# WAB_1_1_top_level.net
KiCad netlist of a schematic drawn in Altium Designer
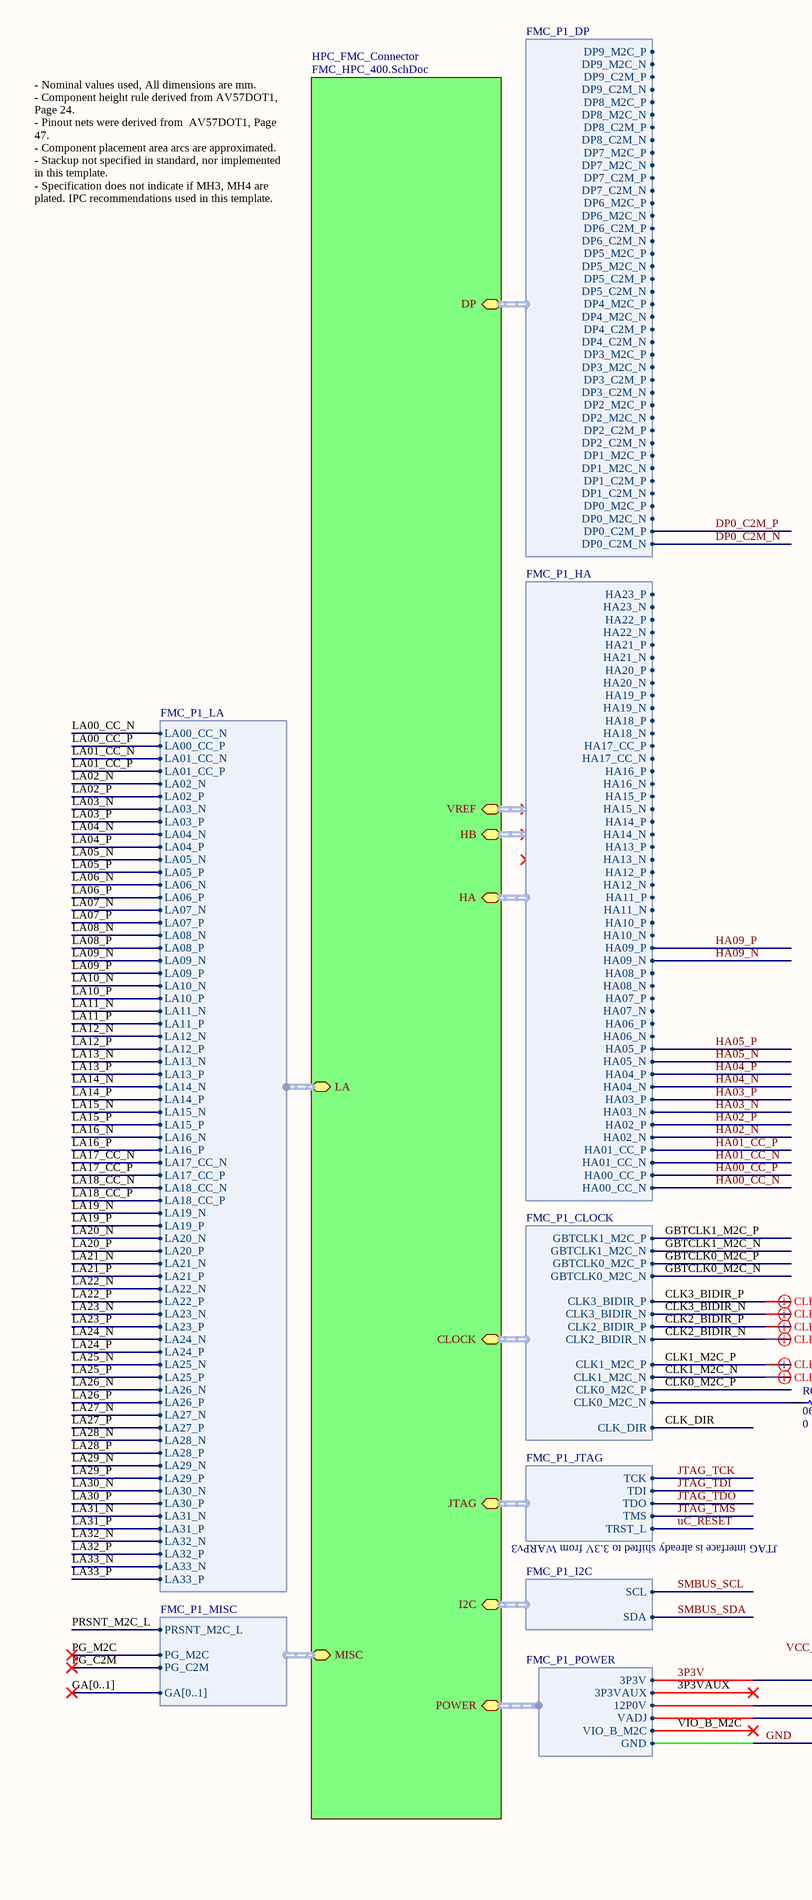
[diagram p0: WAB_1_1_top_level.SchDoc, left]
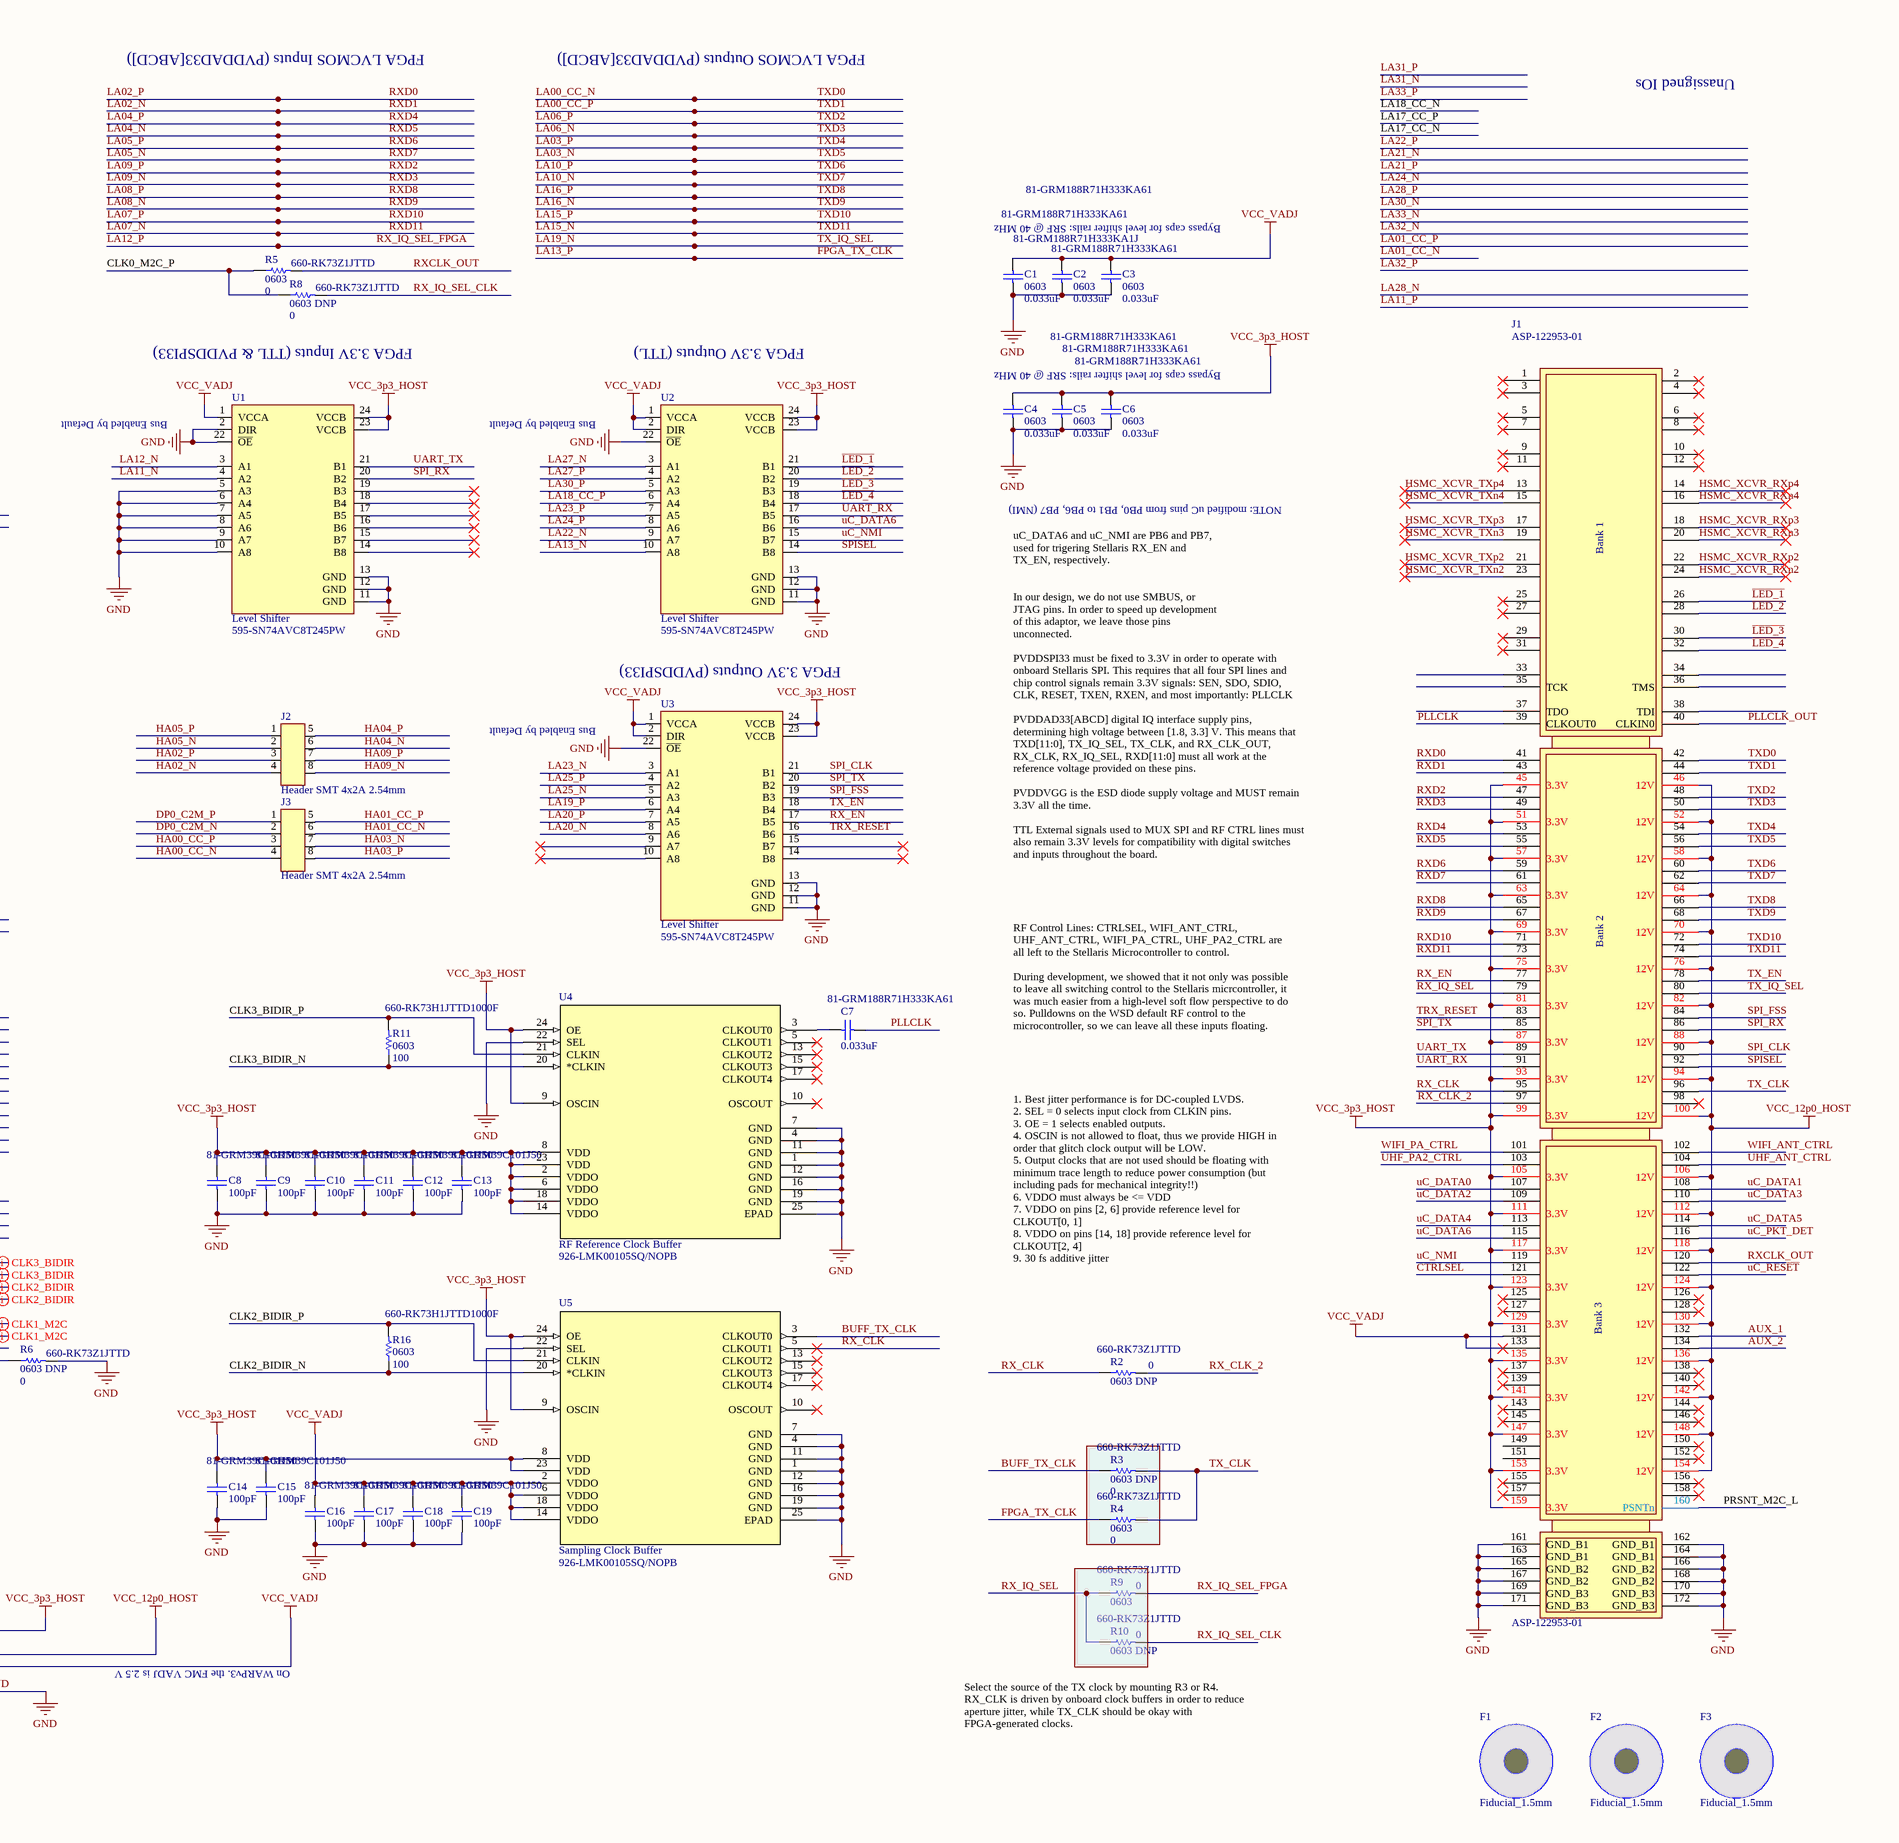
[diagram p1: WAB_1_1_top_level.SchDoc, right]

(export (version "E")
  (design (tool "Eeschema 10.0.6"))
  (components
    (comp (ref "C1")
      (value "0603")
      (footprint "RNG_Footprints:0603_SMT_v3")
      (description "Capacitor (Semiconductor SIM Model)")
      (fields
        (field (name "ALTIUM_VALUE") "0.033uF")
        (field (name "SUPPLIER PART NUMBER 1") "81-GRM188R71H333KA1J")
        (field (name "SUPPLIER PART NUMBER 2") "81-GRM188R71H333KA61")
      )
      (libsource (lib "Miscellaneous Devices") (part "Cap Semi"))
    )
    (comp (ref "C2")
      (value "0603")
      (footprint "RNG_Footprints:0603_SMT_v3")
      (description "Capacitor (Semiconductor SIM Model)")
      (fields
        (field (name "ALTIUM_VALUE") "0.033uF")
        (field (name "SUPPLIER PART NUMBER 2") "81-GRM188R71H333KA61")
      )
      (libsource (lib "Miscellaneous Devices") (part "Cap Semi"))
    )
    (comp (ref "C3")
      (value "0603")
      (footprint "RNG_Footprints:0603_SMT_v3")
      (description "Capacitor (Semiconductor SIM Model)")
      (fields
        (field (name "ALTIUM_VALUE") "0.033uF")
        (field (name "SUPPLIER PART NUMBER 2") "81-GRM188R71H333KA61")
      )
      (libsource (lib "Miscellaneous Devices") (part "Cap Semi"))
    )
    (comp (ref "C4")
      (value "0603")
      (footprint "RNG_Footprints:0603_SMT_v3")
      (description "Capacitor (Semiconductor SIM Model)")
      (fields
        (field (name "ALTIUM_VALUE") "0.033uF")
        (field (name "SUPPLIER PART NUMBER 2") "81-GRM188R71H333KA61")
      )
      (libsource (lib "Miscellaneous Devices") (part "Cap Semi"))
    )
    (comp (ref "C5")
      (value "0603")
      (footprint "RNG_Footprints:0603_SMT_v3")
      (description "Capacitor (Semiconductor SIM Model)")
      (fields
        (field (name "ALTIUM_VALUE") "0.033uF")
        (field (name "SUPPLIER PART NUMBER 2") "81-GRM188R71H333KA61")
      )
      (libsource (lib "Miscellaneous Devices") (part "Cap Semi"))
    )
    (comp (ref "C6")
      (value "0603")
      (footprint "RNG_Footprints:0603_SMT_v3")
      (description "Capacitor (Semiconductor SIM Model)")
      (fields
        (field (name "ALTIUM_VALUE") "0.033uF")
        (field (name "SUPPLIER PART NUMBER 2") "81-GRM188R71H333KA61")
      )
      (libsource (lib "Miscellaneous Devices") (part "Cap Semi"))
    )
    (comp (ref "C7")
      (value "0.033uF")
      (footprint "0603_SMT_v3")
      (fields (field (name "SUPPLIER PART NUMBER 1") "81-GRM188R71H333KA61") (field (name "Comment") "0603"))
      (libsource (lib "RNG_Parts") (part "Cap_0603"))
    )
    (comp (ref "C8")
      (value "100pF")
      (footprint "0603_SMT_v3")
      (fields (field (name "SUPPLIER PART NUMBER 1") "81-GRM39C101J50") (field (name "Comment") "0603"))
      (libsource (lib "RNG_Parts") (part "Cap_0603"))
    )
    (comp (ref "C9")
      (value "100pF")
      (footprint "0603_SMT_v3")
      (fields (field (name "SUPPLIER PART NUMBER 1") "81-GRM39C101J50") (field (name "Comment") "0603"))
      (libsource (lib "RNG_Parts") (part "Cap_0603"))
    )
    (comp (ref "C10")
      (value "100pF")
      (footprint "0603_SMT_v3")
      (fields (field (name "SUPPLIER PART NUMBER 1") "81-GRM39C101J50") (field (name "Comment") "0603"))
      (libsource (lib "RNG_Parts") (part "Cap_0603"))
    )
    (comp (ref "C11")
      (value "100pF")
      (footprint "0603_SMT_v3")
      (fields (field (name "SUPPLIER PART NUMBER 1") "81-GRM39C101J50") (field (name "Comment") "0603"))
      (libsource (lib "RNG_Parts") (part "Cap_0603"))
    )
    (comp (ref "C12")
      (value "100pF")
      (footprint "0603_SMT_v3")
      (fields (field (name "SUPPLIER PART NUMBER 1") "81-GRM39C101J50") (field (name "Comment") "0603"))
      (libsource (lib "RNG_Parts") (part "Cap_0603"))
    )
    (comp (ref "C13")
      (value "100pF")
      (footprint "0603_SMT_v3")
      (fields (field (name "SUPPLIER PART NUMBER 1") "81-GRM39C101J50") (field (name "Comment") "0603"))
      (libsource (lib "RNG_Parts") (part "Cap_0603"))
    )
    (comp (ref "C14")
      (value "100pF")
      (footprint "0603_SMT_v3")
      (fields (field (name "SUPPLIER PART NUMBER 1") "81-GRM39C101J50") (field (name "Comment") "0603"))
      (libsource (lib "RNG_Parts") (part "Cap_0603"))
    )
    (comp (ref "C15")
      (value "100pF")
      (footprint "0603_SMT_v3")
      (fields (field (name "SUPPLIER PART NUMBER 1") "81-GRM39C101J50") (field (name "Comment") "0603"))
      (libsource (lib "RNG_Parts") (part "Cap_0603"))
    )
    (comp (ref "C16")
      (value "100pF")
      (footprint "0603_SMT_v3")
      (fields (field (name "SUPPLIER PART NUMBER 1") "81-GRM39C101J50") (field (name "Comment") "0603"))
      (libsource (lib "RNG_Parts") (part "Cap_0603"))
    )
    (comp (ref "C17")
      (value "100pF")
      (footprint "0603_SMT_v3")
      (fields (field (name "SUPPLIER PART NUMBER 1") "81-GRM39C101J50") (field (name "Comment") "0603"))
      (libsource (lib "RNG_Parts") (part "Cap_0603"))
    )
    (comp (ref "C18")
      (value "100pF")
      (footprint "0603_SMT_v3")
      (fields (field (name "SUPPLIER PART NUMBER 1") "81-GRM39C101J50") (field (name "Comment") "0603"))
      (libsource (lib "RNG_Parts") (part "Cap_0603"))
    )
    (comp (ref "C19")
      (value "100pF")
      (footprint "0603_SMT_v3")
      (fields (field (name "SUPPLIER PART NUMBER 1") "81-GRM39C101J50") (field (name "Comment") "0603"))
      (libsource (lib "RNG_Parts") (part "Cap_0603"))
    )
    (comp (ref "F1")
      (value "Fiducial_1.5mm")
      (footprint "1.5mm_FIDUCIAL_v4")
      (libsource (lib "RNG_Parts") (part "Fiducial_1.5mm"))
    )
    (comp (ref "F2")
      (value "Fiducial_1.5mm")
      (footprint "1.5mm_FIDUCIAL_v4")
      (libsource (lib "RNG_Parts") (part "Fiducial_1.5mm"))
    )
    (comp (ref "F3")
      (value "Fiducial_1.5mm")
      (footprint "1.5mm_FIDUCIAL_v4")
      (libsource (lib "RNG_Parts") (part "Fiducial_1.5mm"))
    )
    (comp (ref "J1")
      (value "ASP-122953-01")
      (footprint "ASP-122953-01_v2")
      (description "Samtec HSMC Host Connector (Female)")
      (libsource (lib "RNG_Parts") (part "ASP-122953-01"))
    )
    (comp (ref "J2")
      (value "Header SMT 4x2A 2.54mm")
      (footprint "2.54mm_4x2_HDR")
      (libsource (lib "RNG_Parts") (part "Header SMT 4x2A 2.54mm"))
    )
    (comp (ref "J3")
      (value "Header SMT 4x2A 2.54mm")
      (footprint "2.54mm_4x2_HDR")
      (libsource (lib "RNG_Parts") (part "Header SMT 4x2A 2.54mm"))
    )
    (comp (ref "R2")
      (value "0603 DNP")
      (footprint "0603_SMT_v3")
      (description "0603 SMT Resistor")
      (fields (field (name "ALTIUM_VALUE") "0") (field (name "SUPPLIER PART NUMBER 1") "660-RK73Z1JTTD"))
      (libsource (lib "RNG_Parts") (part "Res_0603"))
    )
    (comp (ref "R3")
      (value "0603 DNP")
      (footprint "0603_SMT_v3")
      (description "0603 SMT Resistor")
      (fields (field (name "ALTIUM_VALUE") "0") (field (name "SUPPLIER PART NUMBER 1") "660-RK73Z1JTTD"))
      (libsource (lib "RNG_Parts") (part "Res_0603"))
    )
    (comp (ref "R4")
      (value "0603")
      (footprint "0603_SMT_v3")
      (description "0603 SMT Resistor")
      (fields (field (name "ALTIUM_VALUE") "0") (field (name "SUPPLIER PART NUMBER 1") "660-RK73Z1JTTD"))
      (libsource (lib "RNG_Parts") (part "Res_0603"))
    )
    (comp (ref "R5")
      (value "0603")
      (footprint "0603_SMT_v3")
      (description "0603 SMT Resistor")
      (fields (field (name "ALTIUM_VALUE") "0") (field (name "SUPPLIER PART NUMBER 1") "660-RK73Z1JTTD"))
      (libsource (lib "RNG_Parts") (part "Res_0603"))
    )
    (comp (ref "R6")
      (value "0603 DNP")
      (footprint "0603_SMT_v3")
      (description "0603 SMT Resistor")
      (fields (field (name "ALTIUM_VALUE") "0") (field (name "SUPPLIER PART NUMBER 1") "660-RK73Z1JTTD"))
      (libsource (lib "RNG_Parts") (part "Res_0603"))
    )
    (comp (ref "R8")
      (value "0603 DNP")
      (footprint "0603_SMT_v3")
      (description "0603 SMT Resistor")
      (fields (field (name "ALTIUM_VALUE") "0") (field (name "SUPPLIER PART NUMBER 1") "660-RK73Z1JTTD"))
      (libsource (lib "RNG_Parts") (part "Res_0603"))
    )
    (comp (ref "R9")
      (value "0603")
      (footprint "0603_SMT_v3")
      (description "0603 SMT Resistor")
      (fields (field (name "ALTIUM_VALUE") "0") (field (name "SUPPLIER PART NUMBER 1") "660-RK73Z1JTTD"))
      (libsource (lib "RNG_Parts") (part "Res_0603"))
    )
    (comp (ref "R10")
      (value "0603 DNP")
      (footprint "0603_SMT_v3")
      (description "0603 SMT Resistor")
      (fields (field (name "ALTIUM_VALUE") "0") (field (name "SUPPLIER PART NUMBER 1") "660-RK73Z1JTTD"))
      (libsource (lib "RNG_Parts") (part "Res_0603"))
    )
    (comp (ref "R11")
      (value "0603")
      (footprint "0603_SMT_v3")
      (description "0603 SMT Resistor")
      (fields
        (field (name "ALTIUM_VALUE") "100")
        (field (name "SUPPLIER PART NUMBER 1") "660-RK73H1JTTD1000F")
      )
      (libsource (lib "RNG_Parts") (part "Res_0603"))
    )
    (comp (ref "R16")
      (value "0603")
      (footprint "0603_SMT_v3")
      (description "0603 SMT Resistor")
      (fields
        (field (name "ALTIUM_VALUE") "100")
        (field (name "SUPPLIER PART NUMBER 1") "660-RK73H1JTTD1000F")
      )
      (libsource (lib "RNG_Parts") (part "Res_0603"))
    )
    (comp (ref "U1")
      (value "Level Shifter")
      (footprint "TSSOP-24_TI")
      (description "8-bit Dual Supply Bus Transceiver")
      (fields (field (name "SUPPLIER PART NUMBER 1") "595-SN74AVC8T245PW"))
      (libsource (lib "RNG_Parts") (part "SN74AVC8T245PW"))
    )
    (comp (ref "U2")
      (value "Level Shifter")
      (footprint "TSSOP-24_TI")
      (description "8-bit Dual Supply Bus Transceiver")
      (fields (field (name "SUPPLIER PART NUMBER 1") "595-SN74AVC8T245PW"))
      (libsource (lib "RNG_Parts") (part "SN74AVC8T245PW"))
    )
    (comp (ref "U3")
      (value "Level Shifter")
      (footprint "TSSOP-24_TI")
      (description "8-bit Dual Supply Bus Transceiver")
      (fields (field (name "SUPPLIER PART NUMBER 1") "595-SN74AVC8T245PW"))
      (libsource (lib "RNG_Parts") (part "SN74AVC8T245PW"))
    )
    (comp (ref "U4")
      (value "RF Reference Clock Buffer")
      (footprint "RTW24")
      (description "TI Universal-to-CMOS 5-Output Clock Buffer")
      (fields
        (field (name "MANUFACTURER_PART_NUMBER") "lmk00105_rtw_24")
        (field (name "SUPPLIER PART NUMBER 1") "926-LMK00105SQ/NOPB")
      )
      (libsource (lib "RNG_Parts") (part "LMK00105_RTW_24"))
    )
    (comp (ref "U5")
      (value "Sampling Clock Buffer")
      (footprint "RTW24")
      (description "TI Universal-to-CMOS 5-Output Clock Buffer")
      (fields
        (field (name "MANUFACTURER_PART_NUMBER") "lmk00105_rtw_24")
        (field (name "SUPPLIER PART NUMBER 1") "926-LMK00105SQ/NOPB")
      )
      (libsource (lib "RNG_Parts") (part "LMK00105_RTW_24"))
    )
  )
  (nets
    (net (code "12") (name "/AUX_1") (class "Default")
      (node (ref "J1") (pin "132") (pinfunction "132_132") (pintype "passive"))
    )
    (net (code "13") (name "/AUX_2") (class "Default")
      (node (ref "J1") (pin "134") (pinfunction "134_134") (pintype "passive"))
    )
    (net (code "14") (name "/BUFF_TX_CLK") (class "Default")
      (node (ref "R3") (pin "1") (pinfunction "1_1") (pintype "passive"))
      (node (ref "U5") (pin "3") (pinfunction "CLKOUT0_3") (pintype "output"))
    )
    (net (code "15") (name "/CLK0_M2C_N") (class "Default")
      (node (ref "R6") (pin "1") (pinfunction "1_1") (pintype "passive"))
    )
    (net (code "16") (name "/CLK0_M2C_P") (class "Default")
      (node (ref "R5") (pin "1") (pinfunction "1_1") (pintype "passive"))
      (node (ref "R8") (pin "1") (pinfunction "1_1") (pintype "passive"))
    )
    (net (code "19") (name "/CLK2_BIDIR_N") (class "Default")
      (node (ref "R16") (pin "1") (pinfunction "1_1") (pintype "passive"))
      (node (ref "U5") (pin "20") (pinfunction "*CLKIN_20") (pintype "input"))
    )
    (net (code "20") (name "/CLK2_BIDIR_P") (class "Default")
      (node (ref "R16") (pin "2") (pinfunction "2_2") (pintype "passive"))
      (node (ref "U5") (pin "21") (pinfunction "CLKIN_21") (pintype "input"))
    )
    (net (code "21") (name "/CLK3_BIDIR_N") (class "Default")
      (node (ref "R11") (pin "1") (pinfunction "1_1") (pintype "passive"))
      (node (ref "U4") (pin "20") (pinfunction "*CLKIN_20") (pintype "input"))
    )
    (net (code "22") (name "/CLK3_BIDIR_P") (class "Default")
      (node (ref "R11") (pin "2") (pinfunction "2_2") (pintype "passive"))
      (node (ref "U4") (pin "21") (pinfunction "CLKIN_21") (pintype "input"))
    )
    (net (code "24") (name "/CTRLSEL") (class "Default")
      (node (ref "J1") (pin "121") (pinfunction "121_121") (pintype "passive"))
    )
    (net (code "25") (name "/DP0_C2M_N") (class "Default")
      (node (ref "J3") (pin "2") (pinfunction "2_2") (pintype "passive"))
    )
    (net (code "26") (name "/DP0_C2M_P") (class "Default")
      (node (ref "J3") (pin "1") (pinfunction "1_1") (pintype "passive"))
    )
    (net (code "27") (name "/FPGA_TX_CLK") (class "Default")
      (node (ref "R4") (pin "1") (pinfunction "1_1") (pintype "passive"))
    )
    (net (code "33") (name "/HA00_CC_N") (class "Default")
      (node (ref "J3") (pin "4") (pinfunction "4_4") (pintype "passive"))
    )
    (net (code "34") (name "/HA00_CC_P") (class "Default")
      (node (ref "J3") (pin "3") (pinfunction "3_3") (pintype "passive"))
    )
    (net (code "35") (name "/HA01_CC_N") (class "Default")
      (node (ref "J3") (pin "6") (pinfunction "6_6") (pintype "passive"))
    )
    (net (code "36") (name "/HA01_CC_P") (class "Default")
      (node (ref "J3") (pin "5") (pinfunction "5_5") (pintype "passive"))
    )
    (net (code "37") (name "/HA02_N") (class "Default")
      (node (ref "J2") (pin "4") (pinfunction "4_4") (pintype "passive"))
    )
    (net (code "38") (name "/HA02_P") (class "Default")
      (node (ref "J2") (pin "3") (pinfunction "3_3") (pintype "passive"))
    )
    (net (code "39") (name "/HA03_N") (class "Default")
      (node (ref "J3") (pin "7") (pinfunction "7_7") (pintype "passive"))
    )
    (net (code "40") (name "/HA03_P") (class "Default")
      (node (ref "J3") (pin "8") (pinfunction "8_8") (pintype "passive"))
    )
    (net (code "41") (name "/HA04_N") (class "Default")
      (node (ref "J2") (pin "6") (pinfunction "6_6") (pintype "passive"))
    )
    (net (code "42") (name "/HA04_P") (class "Default")
      (node (ref "J2") (pin "5") (pinfunction "5_5") (pintype "passive"))
    )
    (net (code "43") (name "/HA05_N") (class "Default")
      (node (ref "J2") (pin "2") (pinfunction "2_2") (pintype "passive"))
    )
    (net (code "44") (name "/HA05_P") (class "Default")
      (node (ref "J2") (pin "1") (pinfunction "1_1") (pintype "passive"))
    )
    (net (code "45") (name "/HA09_N") (class "Default")
      (node (ref "J2") (pin "8") (pinfunction "8_8") (pintype "passive"))
    )
    (net (code "46") (name "/HA09_P") (class "Default")
      (node (ref "J2") (pin "7") (pinfunction "7_7") (pintype "passive"))
    )
    (net (code "48") (name "/HSMC_XCVR_RXn2") (class "Default")
      (node (ref "J1") (pin "24") (pinfunction "24_24") (pintype "passive+no_connect"))
    )
    (net (code "49") (name "/HSMC_XCVR_RXn3") (class "Default")
      (node (ref "J1") (pin "20") (pinfunction "20_20") (pintype "passive+no_connect"))
    )
    (net (code "50") (name "/HSMC_XCVR_RXn4") (class "Default")
      (node (ref "J1") (pin "16") (pinfunction "16_16") (pintype "passive+no_connect"))
    )
    (net (code "51") (name "/HSMC_XCVR_RXp2") (class "Default")
      (node (ref "J1") (pin "22") (pinfunction "22_22") (pintype "passive"))
    )
    (net (code "52") (name "/HSMC_XCVR_RXp3") (class "Default")
      (node (ref "J1") (pin "18") (pinfunction "18_18") (pintype "passive+no_connect"))
    )
    (net (code "53") (name "/HSMC_XCVR_RXp4") (class "Default")
      (node (ref "J1") (pin "14") (pinfunction "14_14") (pintype "passive+no_connect"))
    )
    (net (code "54") (name "/HSMC_XCVR_TXn2") (class "Default")
      (node (ref "J1") (pin "23") (pinfunction "23_23") (pintype "passive+no_connect"))
    )
    (net (code "55") (name "/HSMC_XCVR_TXn3") (class "Default")
      (node (ref "J1") (pin "19") (pinfunction "19_19") (pintype "passive+no_connect"))
    )
    (net (code "56") (name "/HSMC_XCVR_TXn4") (class "Default")
      (node (ref "J1") (pin "15") (pinfunction "15_15") (pintype "passive+no_connect"))
    )
    (net (code "57") (name "/HSMC_XCVR_TXp2") (class "Default")
      (node (ref "J1") (pin "21") (pinfunction "21_21") (pintype "passive+no_connect"))
    )
    (net (code "58") (name "/HSMC_XCVR_TXp3") (class "Default")
      (node (ref "J1") (pin "17") (pinfunction "17_17") (pintype "passive+no_connect"))
    )
    (net (code "59") (name "/HSMC_XCVR_TXp4") (class "Default")
      (node (ref "J1") (pin "13") (pinfunction "13_13") (pintype "passive+no_connect"))
    )
    (net (code "64") (name "/LA00_CC_N") (class "Default")
      (node (ref "J1") (pin "42") (pinfunction "42_42") (pintype "passive"))
    )
    (net (code "65") (name "/LA00_CC_P") (class "Default")
      (node (ref "J1") (pin "44") (pinfunction "44_44") (pintype "passive"))
    )
    (net (code "68") (name "/LA02_N") (class "Default")
      (node (ref "J1") (pin "43") (pinfunction "43_43") (pintype "passive"))
    )
    (net (code "69") (name "/LA02_P") (class "Default")
      (node (ref "J1") (pin "41") (pinfunction "41_41") (pintype "passive"))
    )
    (net (code "70") (name "/LA03_N") (class "Default")
      (node (ref "J1") (pin "56") (pinfunction "56_56") (pintype "passive"))
    )
    (net (code "71") (name "/LA03_P") (class "Default")
      (node (ref "J1") (pin "54") (pinfunction "54_54") (pintype "passive"))
    )
    (net (code "72") (name "/LA04_N") (class "Default")
      (node (ref "J1") (pin "55") (pinfunction "55_55") (pintype "passive"))
    )
    (net (code "73") (name "/LA04_P") (class "Default")
      (node (ref "J1") (pin "53") (pinfunction "53_53") (pintype "passive"))
    )
    (net (code "74") (name "/LA05_N") (class "Default")
      (node (ref "J1") (pin "61") (pinfunction "61_61") (pintype "passive"))
    )
    (net (code "75") (name "/LA05_P") (class "Default")
      (node (ref "J1") (pin "59") (pinfunction "59_59") (pintype "passive"))
    )
    (net (code "76") (name "/LA06_N") (class "Default")
      (node (ref "J1") (pin "50") (pinfunction "50_50") (pintype "passive"))
    )
    (net (code "77") (name "/LA06_P") (class "Default")
      (node (ref "J1") (pin "48") (pinfunction "48_48") (pintype "passive"))
    )
    (net (code "78") (name "/LA07_N") (class "Default")
      (node (ref "J1") (pin "73") (pinfunction "73_73") (pintype "passive"))
    )
    (net (code "79") (name "/LA07_P") (class "Default")
      (node (ref "J1") (pin "71") (pinfunction "71_71") (pintype "passive"))
    )
    (net (code "80") (name "/LA08_N") (class "Default")
      (node (ref "J1") (pin "67") (pinfunction "67_67") (pintype "passive"))
    )
    (net (code "81") (name "/LA08_P") (class "Default")
      (node (ref "J1") (pin "65") (pinfunction "65_65") (pintype "passive"))
    )
    (net (code "82") (name "/LA09_N") (class "Default")
      (node (ref "J1") (pin "49") (pinfunction "49_49") (pintype "passive"))
    )
    (net (code "83") (name "/LA09_P") (class "Default")
      (node (ref "J1") (pin "47") (pinfunction "47_47") (pintype "passive"))
    )
    (net (code "84") (name "/LA10_N") (class "Default")
      (node (ref "J1") (pin "62") (pinfunction "62_62") (pintype "passive"))
    )
    (net (code "85") (name "/LA10_P") (class "Default")
      (node (ref "J1") (pin "60") (pinfunction "60_60") (pintype "passive"))
    )
    (net (code "86") (name "/LA11_N") (class "Default")
      (node (ref "U1") (pin "4") (pinfunction "A2_4") (pintype "passive"))
    )
    (net (code "88") (name "/LA12_N") (class "Default")
      (node (ref "U1") (pin "3") (pinfunction "A1_3") (pintype "passive"))
    )
    (net (code "89") (name "/LA12_P") (class "Default")
      (node (ref "R9") (pin "2") (pinfunction "2_2") (pintype "passive"))
    )
    (net (code "90") (name "/LA13_N") (class "Default")
      (node (ref "U2") (pin "10") (pinfunction "A8_10") (pintype "passive"))
    )
    (net (code "93") (name "/LA15_N") (class "Default")
      (node (ref "J1") (pin "74") (pinfunction "74_74") (pintype "passive"))
    )
    (net (code "94") (name "/LA15_P") (class "Default")
      (node (ref "J1") (pin "72") (pinfunction "72_72") (pintype "passive"))
    )
    (net (code "95") (name "/LA16_N") (class "Default")
      (node (ref "J1") (pin "68") (pinfunction "68_68") (pintype "passive"))
    )
    (net (code "96") (name "/LA16_P") (class "Default")
      (node (ref "J1") (pin "66") (pinfunction "66_66") (pintype "passive"))
    )
    (net (code "100") (name "/LA18_CC_P") (class "Default")
      (node (ref "U2") (pin "6") (pinfunction "A4_6") (pintype "passive"))
    )
    (net (code "101") (name "/LA19_N") (class "Default")
      (node (ref "J1") (pin "80") (pinfunction "80_80") (pintype "passive"))
    )
    (net (code "102") (name "/LA19_P") (class "Default")
      (node (ref "U3") (pin "6") (pinfunction "A4_6") (pintype "passive"))
    )
    (net (code "103") (name "/LA20_N") (class "Default")
      (node (ref "U3") (pin "8") (pinfunction "A6_8") (pintype "passive"))
    )
    (net (code "104") (name "/LA20_P") (class "Default")
      (node (ref "U3") (pin "7") (pinfunction "A5_7") (pintype "passive"))
    )
    (net (code "107") (name "/LA22_N") (class "Default")
      (node (ref "U2") (pin "9") (pinfunction "A7_9") (pintype "passive"))
    )
    (net (code "109") (name "/LA23_N") (class "Default")
      (node (ref "U3") (pin "3") (pinfunction "A1_3") (pintype "passive"))
    )
    (net (code "110") (name "/LA23_P") (class "Default")
      (node (ref "U2") (pin "7") (pinfunction "A5_7") (pintype "passive"))
    )
    (net (code "112") (name "/LA24_P") (class "Default")
      (node (ref "U2") (pin "8") (pinfunction "A6_8") (pintype "passive"))
    )
    (net (code "113") (name "/LA25_N") (class "Default")
      (node (ref "U3") (pin "5") (pinfunction "A3_5") (pintype "passive"))
    )
    (net (code "114") (name "/LA25_P") (class "Default")
      (node (ref "U3") (pin "4") (pinfunction "A2_4") (pintype "passive"))
    )
    (net (code "117") (name "/LA27_N") (class "Default")
      (node (ref "U2") (pin "3") (pinfunction "A1_3") (pintype "passive"))
    )
    (net (code "118") (name "/LA27_P") (class "Default")
      (node (ref "U2") (pin "4") (pinfunction "A2_4") (pintype "passive"))
    )
    (net (code "124") (name "/LA30_P") (class "Default")
      (node (ref "U2") (pin "5") (pinfunction "A3_5") (pintype "passive"))
    )
    (net (code "131") (name "/LED_1") (class "Default")
      (node (ref "J1") (pin "26") (pinfunction "26_26") (pintype "passive"))
      (node (ref "U2") (pin "21") (pinfunction "B1_21") (pintype "passive"))
    )
    (net (code "132") (name "/LED_2") (class "Default")
      (node (ref "J1") (pin "28") (pinfunction "28_28") (pintype "passive"))
      (node (ref "U2") (pin "20") (pinfunction "B2_20") (pintype "passive"))
    )
    (net (code "133") (name "/LED_3") (class "Default")
      (node (ref "J1") (pin "30") (pinfunction "30_30") (pintype "passive"))
      (node (ref "U2") (pin "19") (pinfunction "B3_19") (pintype "passive"))
    )
    (net (code "134") (name "/LED_4") (class "Default")
      (node (ref "J1") (pin "32") (pinfunction "32_32") (pintype "passive"))
      (node (ref "U2") (pin "18") (pinfunction "B4_18") (pintype "passive"))
    )
    (net (code "137") (name "/PLLCLK") (class "Default")
      (node (ref "C7") (pin "1") (pinfunction "1_1") (pintype "passive"))
      (node (ref "J1") (pin "39") (pinfunction "CLKOUT0_39") (pintype "power_in"))
    )
    (net (code "138") (name "/PLLCLK_OUT") (class "Default")
      (node (ref "J1") (pin "40") (pinfunction "CLKIN0_40") (pintype "power_in"))
    )
    (net (code "139") (name "/PRSNT_M2C_L") (class "Default")
      (node (ref "J1") (pin "160") (pinfunction "PSNTn_160") (pintype "power_in"))
    )
    (net (code "140") (name "/RXCLK_OUT") (class "Default")
      (node (ref "J1") (pin "120") (pinfunction "120_120") (pintype "passive"))
      (node (ref "R5") (pin "2") (pinfunction "2_2") (pintype "passive"))
    )
    (net (code "141") (name "/RX_CLK") (class "Default")
      (node (ref "J1") (pin "95") (pinfunction "95_95") (pintype "passive"))
      (node (ref "R2") (pin "1") (pinfunction "1_1") (pintype "passive"))
      (node (ref "U5") (pin "5") (pinfunction "CLKOUT1_5") (pintype "output"))
    )
    (net (code "142") (name "/RX_CLK_2") (class "Default")
      (node (ref "J1") (pin "97") (pinfunction "97_97") (pintype "passive"))
      (node (ref "R2") (pin "2") (pinfunction "2_2") (pintype "passive"))
    )
    (net (code "143") (name "/RX_EN") (class "Default")
      (node (ref "J1") (pin "77") (pinfunction "77_77") (pintype "passive"))
      (node (ref "U3") (pin "17") (pinfunction "B5_17") (pintype "passive"))
    )
    (net (code "144") (name "/RX_IQ_SEL") (class "Default")
      (node (ref "J1") (pin "79") (pinfunction "79_79") (pintype "passive"))
      (node (ref "R10") (pin "1") (pinfunction "1_1") (pintype "passive"))
      (node (ref "R9") (pin "1") (pinfunction "1_1") (pintype "passive"))
    )
    (net (code "145") (name "/RX_IQ_SEL_CLK") (class "Default")
      (node (ref "R10") (pin "2") (pinfunction "2_2") (pintype "passive"))
      (node (ref "R8") (pin "2") (pinfunction "2_2") (pintype "passive"))
    )
    (net (code "148") (name "/SPISEL") (class "Default")
      (node (ref "J1") (pin "92") (pinfunction "92_92") (pintype "passive"))
      (node (ref "U2") (pin "14") (pinfunction "B8_14") (pintype "passive"))
    )
    (net (code "149") (name "/SPI_CLK") (class "Default")
      (node (ref "J1") (pin "90") (pinfunction "90_90") (pintype "passive"))
      (node (ref "U3") (pin "21") (pinfunction "B1_21") (pintype "passive"))
    )
    (net (code "150") (name "/SPI_FSS") (class "Default")
      (node (ref "J1") (pin "84") (pinfunction "84_84") (pintype "passive"))
      (node (ref "U3") (pin "19") (pinfunction "B3_19") (pintype "passive"))
    )
    (net (code "151") (name "/SPI_RX") (class "Default")
      (node (ref "J1") (pin "86") (pinfunction "86_86") (pintype "passive"))
      (node (ref "U1") (pin "20") (pinfunction "B2_20") (pintype "passive"))
    )
    (net (code "152") (name "/SPI_TX") (class "Default")
      (node (ref "J1") (pin "85") (pinfunction "85_85") (pintype "passive"))
      (node (ref "U3") (pin "20") (pinfunction "B2_20") (pintype "passive"))
    )
    (net (code "153") (name "/TRX_RESET") (class "Default")
      (node (ref "J1") (pin "83") (pinfunction "83_83") (pintype "passive"))
      (node (ref "U3") (pin "16") (pinfunction "B6_16") (pintype "passive"))
    )
    (net (code "154") (name "/TX_CLK") (class "Default")
      (node (ref "J1") (pin "96") (pinfunction "96_96") (pintype "passive"))
      (node (ref "R3") (pin "2") (pinfunction "2_2") (pintype "passive"))
      (node (ref "R4") (pin "2") (pinfunction "2_2") (pintype "passive"))
    )
    (net (code "155") (name "/TX_EN") (class "Default")
      (node (ref "J1") (pin "78") (pinfunction "78_78") (pintype "passive"))
      (node (ref "U3") (pin "18") (pinfunction "B4_18") (pintype "passive"))
    )
    (net (code "156") (name "/UART_RX") (class "Default")
      (node (ref "J1") (pin "91") (pinfunction "91_91") (pintype "passive"))
      (node (ref "U2") (pin "17") (pinfunction "B5_17") (pintype "passive"))
    )
    (net (code "157") (name "/UART_TX") (class "Default")
      (node (ref "J1") (pin "89") (pinfunction "89_89") (pintype "passive"))
      (node (ref "U1") (pin "21") (pinfunction "B1_21") (pintype "passive"))
    )
    (net (code "158") (name "/UHF_ANT_CTRL") (class "Default")
      (node (ref "J1") (pin "104") (pinfunction "104_104") (pintype "passive"))
    )
    (net (code "159") (name "/UHF_PA2_CTRL") (class "Default")
      (node (ref "J1") (pin "103") (pinfunction "103_103") (pintype "passive"))
    )
    (net (code "162") (name "/WIFI_ANT_CTRL") (class "Default")
      (node (ref "J1") (pin "102") (pinfunction "102_102") (pintype "passive"))
    )
    (net (code "163") (name "/WIFI_PA_CTRL") (class "Default")
      (node (ref "J1") (pin "101") (pinfunction "101_101") (pintype "passive"))
    )
    (net (code "164") (name "/uC_DATA0") (class "Default")
      (node (ref "J1") (pin "107") (pinfunction "107_107") (pintype "passive"))
    )
    (net (code "165") (name "/uC_DATA1") (class "Default")
      (node (ref "J1") (pin "108") (pinfunction "108_108") (pintype "passive"))
    )
    (net (code "166") (name "/uC_DATA2") (class "Default")
      (node (ref "J1") (pin "109") (pinfunction "109_109") (pintype "passive"))
    )
    (net (code "167") (name "/uC_DATA3") (class "Default")
      (node (ref "J1") (pin "110") (pinfunction "110_110") (pintype "passive"))
    )
    (net (code "168") (name "/uC_DATA4") (class "Default")
      (node (ref "J1") (pin "113") (pinfunction "113_113") (pintype "passive"))
    )
    (net (code "169") (name "/uC_DATA5") (class "Default")
      (node (ref "J1") (pin "114") (pinfunction "114_114") (pintype "passive"))
    )
    (net (code "170") (name "/uC_DATA6") (class "Default")
      (node (ref "J1") (pin "115") (pinfunction "115_115") (pintype "passive"))
      (node (ref "U2") (pin "16") (pinfunction "B6_16") (pintype "passive"))
    )
    (net (code "171") (name "/uC_NMI") (class "Default")
      (node (ref "J1") (pin "119") (pinfunction "119_119") (pintype "passive"))
      (node (ref "U2") (pin "15") (pinfunction "B7_15") (pintype "passive"))
    )
    (net (code "172") (name "/uC_PKT_DET") (class "Default")
      (node (ref "J1") (pin "116") (pinfunction "116_116") (pintype "passive"))
    )
    (net (code "173") (name "/uC_RESET") (class "Default")
      (node (ref "J1") (pin "122") (pinfunction "122_122") (pintype "passive"))
    )
    (net (code "182") (name "GND") (class "Default")
      (node (ref "C1") (pin "1") (pinfunction "1_1") (pintype "passive"))
      (node (ref "C10") (pin "1") (pinfunction "1_1") (pintype "passive"))
      (node (ref "C11") (pin "1") (pinfunction "1_1") (pintype "passive"))
      (node (ref "C12") (pin "1") (pinfunction "1_1") (pintype "passive"))
      (node (ref "C13") (pin "1") (pinfunction "1_1") (pintype "passive"))
      (node (ref "C14") (pin "1") (pinfunction "1_1") (pintype "passive"))
      (node (ref "C15") (pin "1") (pinfunction "1_1") (pintype "passive"))
      (node (ref "C16") (pin "1") (pinfunction "1_1") (pintype "passive"))
      (node (ref "C17") (pin "1") (pinfunction "1_1") (pintype "passive"))
      (node (ref "C18") (pin "1") (pinfunction "1_1") (pintype "passive"))
      (node (ref "C19") (pin "1") (pinfunction "1_1") (pintype "passive"))
      (node (ref "C2") (pin "1") (pinfunction "1_1") (pintype "passive"))
      (node (ref "C3") (pin "1") (pinfunction "1_1") (pintype "passive"))
      (node (ref "C4") (pin "1") (pinfunction "1_1") (pintype "passive"))
      (node (ref "C5") (pin "1") (pinfunction "1_1") (pintype "passive"))
      (node (ref "C6") (pin "1") (pinfunction "1_1") (pintype "passive"))
      (node (ref "C8") (pin "1") (pinfunction "1_1") (pintype "passive"))
      (node (ref "C9") (pin "1") (pinfunction "1_1") (pintype "passive"))
      (node (ref "J1") (pin "161") (pinfunction "GND_B1_161") (pintype "power_in"))
      (node (ref "J1") (pin "162") (pinfunction "GND_B1_162") (pintype "power_in"))
      (node (ref "J1") (pin "163") (pinfunction "GND_B1_163") (pintype "power_in"))
      (node (ref "J1") (pin "164") (pinfunction "GND_B1_164") (pintype "power_in"))
      (node (ref "J1") (pin "165") (pinfunction "GND_B2_165") (pintype "power_in"))
      (node (ref "J1") (pin "166") (pinfunction "GND_B2_166") (pintype "power_in"))
      (node (ref "J1") (pin "167") (pinfunction "GND_B2_167") (pintype "power_in"))
      (node (ref "J1") (pin "168") (pinfunction "GND_B2_168") (pintype "power_in"))
      (node (ref "J1") (pin "169") (pinfunction "GND_B3_169") (pintype "power_in"))
      (node (ref "J1") (pin "170") (pinfunction "GND_B3_170") (pintype "power_in"))
      (node (ref "J1") (pin "171") (pinfunction "GND_B3_171") (pintype "power_in"))
      (node (ref "J1") (pin "172") (pinfunction "GND_B3_172") (pintype "power_in"))
      (node (ref "R6") (pin "2") (pinfunction "2_2") (pintype "passive"))
      (node (ref "U1") (pin "10") (pinfunction "A8_10") (pintype "passive"))
      (node (ref "U1") (pin "11") (pinfunction "GND_11") (pintype "passive"))
      (node (ref "U1") (pin "12") (pinfunction "GND_12") (pintype "passive"))
      (node (ref "U1") (pin "13") (pinfunction "GND_13") (pintype "passive"))
      (node (ref "U1") (pin "2") (pinfunction "DIR_2") (pintype "passive"))
      (node (ref "U1") (pin "22") (pinfunction "OE_22") (pintype "passive"))
      (node (ref "U1") (pin "5") (pinfunction "A3_5") (pintype "passive"))
      (node (ref "U1") (pin "6") (pinfunction "A4_6") (pintype "passive"))
      (node (ref "U1") (pin "7") (pinfunction "A5_7") (pintype "passive"))
      (node (ref "U1") (pin "8") (pinfunction "A6_8") (pintype "passive"))
      (node (ref "U1") (pin "9") (pinfunction "A7_9") (pintype "passive"))
      (node (ref "U2") (pin "11") (pinfunction "GND_11") (pintype "passive"))
      (node (ref "U2") (pin "12") (pinfunction "GND_12") (pintype "passive"))
      (node (ref "U2") (pin "13") (pinfunction "GND_13") (pintype "passive"))
      (node (ref "U2") (pin "22") (pinfunction "OE_22") (pintype "passive"))
      (node (ref "U3") (pin "11") (pinfunction "GND_11") (pintype "passive"))
      (node (ref "U3") (pin "12") (pinfunction "GND_12") (pintype "passive"))
      (node (ref "U3") (pin "13") (pinfunction "GND_13") (pintype "passive"))
      (node (ref "U3") (pin "22") (pinfunction "OE_22") (pintype "passive"))
      (node (ref "U4") (pin "1") (pinfunction "GND_1") (pintype "power_in"))
      (node (ref "U4") (pin "11") (pinfunction "GND_11") (pintype "power_in"))
      (node (ref "U4") (pin "12") (pinfunction "GND_12") (pintype "power_in"))
      (node (ref "U4") (pin "16") (pinfunction "GND_16") (pintype "power_in"))
      (node (ref "U4") (pin "19") (pinfunction "GND_19") (pintype "power_in"))
      (node (ref "U4") (pin "22") (pinfunction "SEL_22") (pintype "input"))
      (node (ref "U4") (pin "25") (pinfunction "EPAD_25") (pintype "passive"))
      (node (ref "U4") (pin "4") (pinfunction "GND_4") (pintype "power_in"))
      (node (ref "U4") (pin "7") (pinfunction "GND_7") (pintype "power_in"))
      (node (ref "U5") (pin "1") (pinfunction "GND_1") (pintype "power_in"))
      (node (ref "U5") (pin "11") (pinfunction "GND_11") (pintype "power_in"))
      (node (ref "U5") (pin "12") (pinfunction "GND_12") (pintype "power_in"))
      (node (ref "U5") (pin "16") (pinfunction "GND_16") (pintype "power_in"))
      (node (ref "U5") (pin "19") (pinfunction "GND_19") (pintype "power_in"))
      (node (ref "U5") (pin "22") (pinfunction "SEL_22") (pintype "input"))
      (node (ref "U5") (pin "25") (pinfunction "EPAD_25") (pintype "passive"))
      (node (ref "U5") (pin "4") (pinfunction "GND_4") (pintype "power_in"))
      (node (ref "U5") (pin "7") (pinfunction "GND_7") (pintype "power_in"))
    )
    (net (code "183") (name "Net-(U4-CLKOUT0)") (class "Default")
      (node (ref "C7") (pin "2") (pinfunction "2_2") (pintype "passive"))
      (node (ref "U4") (pin "3") (pinfunction "CLKOUT0_3") (pintype "output"))
    )
    (net (code "184") (name "VCC_3p3_HOST") (class "Default")
      (node (ref "C10") (pin "2") (pinfunction "2_2") (pintype "passive"))
      (node (ref "C11") (pin "2") (pinfunction "2_2") (pintype "passive"))
      (node (ref "C12") (pin "2") (pinfunction "2_2") (pintype "passive"))
      (node (ref "C13") (pin "2") (pinfunction "2_2") (pintype "passive"))
      (node (ref "C14") (pin "2") (pinfunction "2_2") (pintype "passive"))
      (node (ref "C15") (pin "2") (pinfunction "2_2") (pintype "passive"))
      (node (ref "C4") (pin "2") (pinfunction "2_2") (pintype "passive"))
      (node (ref "C5") (pin "2") (pinfunction "2_2") (pintype "passive"))
      (node (ref "C6") (pin "2") (pinfunction "2_2") (pintype "passive"))
      (node (ref "C8") (pin "2") (pinfunction "2_2") (pintype "passive"))
      (node (ref "C9") (pin "2") (pinfunction "2_2") (pintype "passive"))
      (node (ref "J1") (pin "105") (pinfunction "3.3V_105") (pintype "power_in"))
      (node (ref "J1") (pin "111") (pinfunction "3.3V_111") (pintype "power_in"))
      (node (ref "J1") (pin "117") (pinfunction "3.3V_117") (pintype "power_in"))
      (node (ref "J1") (pin "123") (pinfunction "3.3V_123") (pintype "power_in"))
      (node (ref "J1") (pin "129") (pinfunction "3.3V_129") (pintype "power_in"))
      (node (ref "J1") (pin "135") (pinfunction "3.3V_135") (pintype "power_in"))
      (node (ref "J1") (pin "141") (pinfunction "3.3V_141") (pintype "power_in"))
      (node (ref "J1") (pin "147") (pinfunction "3.3V_147") (pintype "power_in"))
      (node (ref "J1") (pin "153") (pinfunction "3.3V_153") (pintype "power_in"))
      (node (ref "J1") (pin "159") (pinfunction "3.3V_159") (pintype "power_in"))
      (node (ref "J1") (pin "45") (pinfunction "3.3V_45") (pintype "power_in"))
      (node (ref "J1") (pin "51") (pinfunction "3.3V_51") (pintype "power_in"))
      (node (ref "J1") (pin "57") (pinfunction "3.3V_57") (pintype "power_in"))
      (node (ref "J1") (pin "63") (pinfunction "3.3V_63") (pintype "power_in"))
      (node (ref "J1") (pin "69") (pinfunction "3.3V_69") (pintype "power_in"))
      (node (ref "J1") (pin "75") (pinfunction "3.3V_75") (pintype "power_in"))
      (node (ref "J1") (pin "81") (pinfunction "3.3V_81") (pintype "power_in"))
      (node (ref "J1") (pin "87") (pinfunction "3.3V_87") (pintype "power_in"))
      (node (ref "J1") (pin "93") (pinfunction "3.3V_93") (pintype "power_in"))
      (node (ref "J1") (pin "99") (pinfunction "3.3V_99") (pintype "power_in"))
      (node (ref "U1") (pin "23") (pinfunction "VCCB_23") (pintype "passive"))
      (node (ref "U1") (pin "24") (pinfunction "VCCB_24") (pintype "passive"))
      (node (ref "U2") (pin "23") (pinfunction "VCCB_23") (pintype "passive"))
      (node (ref "U2") (pin "24") (pinfunction "VCCB_24") (pintype "passive"))
      (node (ref "U3") (pin "23") (pinfunction "VCCB_23") (pintype "passive"))
      (node (ref "U3") (pin "24") (pinfunction "VCCB_24") (pintype "passive"))
      (node (ref "U4") (pin "14") (pinfunction "VDDO_14") (pintype "power_in"))
      (node (ref "U4") (pin "18") (pinfunction "VDDO_18") (pintype "power_in"))
      (node (ref "U4") (pin "2") (pinfunction "VDDO_2") (pintype "power_in"))
      (node (ref "U4") (pin "23") (pinfunction "VDD_23") (pintype "power_in"))
      (node (ref "U4") (pin "24") (pinfunction "OE_24") (pintype "input"))
      (node (ref "U4") (pin "6") (pinfunction "VDDO_6") (pintype "power_in"))
      (node (ref "U4") (pin "8") (pinfunction "VDD_8") (pintype "power_in"))
      (node (ref "U4") (pin "9") (pinfunction "OSCIN_9") (pintype "input"))
      (node (ref "U5") (pin "23") (pinfunction "VDD_23") (pintype "power_in"))
      (node (ref "U5") (pin "24") (pinfunction "OE_24") (pintype "input"))
      (node (ref "U5") (pin "8") (pinfunction "VDD_8") (pintype "power_in"))
      (node (ref "U5") (pin "9") (pinfunction "OSCIN_9") (pintype "input"))
    )
    (net (code "185") (name "VCC_12p0_HOST") (class "Default")
      (node (ref "J1") (pin "100") (pinfunction "12V_100") (pintype "power_in"))
      (node (ref "J1") (pin "106") (pinfunction "12V_106") (pintype "power_in"))
      (node (ref "J1") (pin "112") (pinfunction "12V_112") (pintype "power_in"))
      (node (ref "J1") (pin "118") (pinfunction "12V_118") (pintype "power_in"))
      (node (ref "J1") (pin "124") (pinfunction "12V_124") (pintype "power_in"))
      (node (ref "J1") (pin "130") (pinfunction "12V_130") (pintype "power_in"))
      (node (ref "J1") (pin "136") (pinfunction "12V_136") (pintype "power_in"))
      (node (ref "J1") (pin "142") (pinfunction "12V_142") (pintype "power_in"))
      (node (ref "J1") (pin "148") (pinfunction "12V_148") (pintype "power_in"))
      (node (ref "J1") (pin "154") (pinfunction "12V_154") (pintype "power_in"))
      (node (ref "J1") (pin "46") (pinfunction "12V_46") (pintype "power_in"))
      (node (ref "J1") (pin "52") (pinfunction "12V_52") (pintype "power_in"))
      (node (ref "J1") (pin "58") (pinfunction "12V_58") (pintype "power_in"))
      (node (ref "J1") (pin "64") (pinfunction "12V_64") (pintype "power_in"))
      (node (ref "J1") (pin "70") (pinfunction "12V_70") (pintype "power_in"))
      (node (ref "J1") (pin "76") (pinfunction "12V_76") (pintype "power_in"))
      (node (ref "J1") (pin "82") (pinfunction "12V_82") (pintype "power_in"))
      (node (ref "J1") (pin "88") (pinfunction "12V_88") (pintype "power_in"))
      (node (ref "J1") (pin "94") (pinfunction "12V_94") (pintype "power_in"))
    )
    (net (code "186") (name "VCC_VADJ") (class "Default")
      (node (ref "C1") (pin "2") (pinfunction "2_2") (pintype "passive"))
      (node (ref "C16") (pin "2") (pinfunction "2_2") (pintype "passive"))
      (node (ref "C17") (pin "2") (pinfunction "2_2") (pintype "passive"))
      (node (ref "C18") (pin "2") (pinfunction "2_2") (pintype "passive"))
      (node (ref "C19") (pin "2") (pinfunction "2_2") (pintype "passive"))
      (node (ref "C2") (pin "2") (pinfunction "2_2") (pintype "passive"))
      (node (ref "C3") (pin "2") (pinfunction "2_2") (pintype "passive"))
      (node (ref "J1") (pin "131") (pinfunction "131_131") (pintype "passive"))
      (node (ref "J1") (pin "133") (pinfunction "133_133") (pintype "passive"))
      (node (ref "U1") (pin "1") (pinfunction "VCCA_1") (pintype "power_in"))
      (node (ref "U2") (pin "1") (pinfunction "VCCA_1") (pintype "power_in"))
      (node (ref "U2") (pin "2") (pinfunction "DIR_2") (pintype "passive"))
      (node (ref "U3") (pin "1") (pinfunction "VCCA_1") (pintype "power_in"))
      (node (ref "U3") (pin "2") (pinfunction "DIR_2") (pintype "passive"))
      (node (ref "U5") (pin "14") (pinfunction "VDDO_14") (pintype "power_in"))
      (node (ref "U5") (pin "18") (pinfunction "VDDO_18") (pintype "power_in"))
      (node (ref "U5") (pin "2") (pinfunction "VDDO_2") (pintype "power_in"))
      (node (ref "U5") (pin "6") (pinfunction "VDDO_6") (pintype "power_in"))
    )
    (net (code "187") (name "unconnected-(J1-Pad1)") (class "Default")
      (node (ref "J1") (pin "1") (pinfunction "1_1") (pintype "passive+no_connect"))
    )
    (net (code "188") (name "unconnected-(J1-Pad2)") (class "Default")
      (node (ref "J1") (pin "2") (pinfunction "2_2") (pintype "passive+no_connect"))
    )
    (net (code "189") (name "unconnected-(J1-Pad3)") (class "Default")
      (node (ref "J1") (pin "3") (pinfunction "3_3") (pintype "passive+no_connect"))
    )
    (net (code "190") (name "unconnected-(J1-Pad4)") (class "Default")
      (node (ref "J1") (pin "4") (pinfunction "4_4") (pintype "passive+no_connect"))
    )
    (net (code "191") (name "unconnected-(J1-Pad5)") (class "Default")
      (node (ref "J1") (pin "5") (pinfunction "5_5") (pintype "passive+no_connect"))
    )
    (net (code "192") (name "unconnected-(J1-Pad6)") (class "Default")
      (node (ref "J1") (pin "6") (pinfunction "6_6") (pintype "passive+no_connect"))
    )
    (net (code "193") (name "unconnected-(J1-Pad7)") (class "Default")
      (node (ref "J1") (pin "7") (pinfunction "7_7") (pintype "passive+no_connect"))
    )
    (net (code "194") (name "unconnected-(J1-Pad8)") (class "Default")
      (node (ref "J1") (pin "8") (pinfunction "8_8") (pintype "passive+no_connect"))
    )
    (net (code "195") (name "unconnected-(J1-Pad9)") (class "Default")
      (node (ref "J1") (pin "9") (pinfunction "9_9") (pintype "passive+no_connect"))
    )
    (net (code "196") (name "unconnected-(J1-Pad10)") (class "Default")
      (node (ref "J1") (pin "10") (pinfunction "10_10") (pintype "passive+no_connect"))
    )
    (net (code "197") (name "unconnected-(J1-Pad11)") (class "Default")
      (node (ref "J1") (pin "11") (pinfunction "11_11") (pintype "passive+no_connect"))
    )
    (net (code "198") (name "unconnected-(J1-Pad12)") (class "Default")
      (node (ref "J1") (pin "12") (pinfunction "12_12") (pintype "passive+no_connect"))
    )
    (net (code "199") (name "unconnected-(J1-Pad25)") (class "Default")
      (node (ref "J1") (pin "25") (pinfunction "25_25") (pintype "passive+no_connect"))
    )
    (net (code "200") (name "unconnected-(J1-Pad27)") (class "Default")
      (node (ref "J1") (pin "27") (pinfunction "27_27") (pintype "passive+no_connect"))
    )
    (net (code "201") (name "unconnected-(J1-Pad29)") (class "Default")
      (node (ref "J1") (pin "29") (pinfunction "29_29") (pintype "passive+no_connect"))
    )
    (net (code "202") (name "unconnected-(J1-Pad31)") (class "Default")
      (node (ref "J1") (pin "31") (pinfunction "31_31") (pintype "passive+no_connect"))
    )
    (net (code "203") (name "unconnected-(J1-Pad98)") (class "Default")
      (node (ref "J1") (pin "98") (pinfunction "98_98") (pintype "passive+no_connect"))
    )
    (net (code "204") (name "unconnected-(J1-Pad125)") (class "Default")
      (node (ref "J1") (pin "125") (pinfunction "125_125") (pintype "passive+no_connect"))
    )
    (net (code "205") (name "unconnected-(J1-Pad126)") (class "Default")
      (node (ref "J1") (pin "126") (pinfunction "126_126") (pintype "passive+no_connect"))
    )
    (net (code "206") (name "unconnected-(J1-Pad127)") (class "Default")
      (node (ref "J1") (pin "127") (pinfunction "127_127") (pintype "passive+no_connect"))
    )
    (net (code "207") (name "unconnected-(J1-Pad128)") (class "Default")
      (node (ref "J1") (pin "128") (pinfunction "128_128") (pintype "passive+no_connect"))
    )
    (net (code "208") (name "unconnected-(J1-Pad137)") (class "Default")
      (node (ref "J1") (pin "137") (pinfunction "137_137") (pintype "passive+no_connect"))
    )
    (net (code "209") (name "unconnected-(J1-Pad138)") (class "Default")
      (node (ref "J1") (pin "138") (pinfunction "138_138") (pintype "passive+no_connect"))
    )
    (net (code "210") (name "unconnected-(J1-Pad139)") (class "Default")
      (node (ref "J1") (pin "139") (pinfunction "139_139") (pintype "passive+no_connect"))
    )
    (net (code "211") (name "unconnected-(J1-Pad140)") (class "Default")
      (node (ref "J1") (pin "140") (pinfunction "140_140") (pintype "passive+no_connect"))
    )
    (net (code "212") (name "unconnected-(J1-Pad143)") (class "Default")
      (node (ref "J1") (pin "143") (pinfunction "143_143") (pintype "passive+no_connect"))
    )
    (net (code "213") (name "unconnected-(J1-Pad144)") (class "Default")
      (node (ref "J1") (pin "144") (pinfunction "144_144") (pintype "passive+no_connect"))
    )
    (net (code "214") (name "unconnected-(J1-Pad145)") (class "Default")
      (node (ref "J1") (pin "145") (pinfunction "145_145") (pintype "passive+no_connect"))
    )
    (net (code "215") (name "unconnected-(J1-Pad146)") (class "Default")
      (node (ref "J1") (pin "146") (pinfunction "146_146") (pintype "passive+no_connect"))
    )
    (net (code "216") (name "unconnected-(J1-Pad149)") (class "Default")
      (node (ref "J1") (pin "149") (pinfunction "149_149") (pintype "passive"))
    )
    (net (code "217") (name "unconnected-(J1-Pad150)") (class "Default")
      (node (ref "J1") (pin "150") (pinfunction "150_150") (pintype "passive+no_connect"))
    )
    (net (code "218") (name "unconnected-(J1-Pad151)") (class "Default")
      (node (ref "J1") (pin "151") (pinfunction "151_151") (pintype "passive"))
    )
    (net (code "219") (name "unconnected-(J1-Pad152)") (class "Default")
      (node (ref "J1") (pin "152") (pinfunction "152_152") (pintype "passive+no_connect"))
    )
    (net (code "220") (name "unconnected-(J1-Pad155)") (class "Default")
      (node (ref "J1") (pin "155") (pinfunction "155_155") (pintype "passive+no_connect"))
    )
    (net (code "221") (name "unconnected-(J1-Pad156)") (class "Default")
      (node (ref "J1") (pin "156") (pinfunction "156_156") (pintype "passive+no_connect"))
    )
    (net (code "222") (name "unconnected-(J1-Pad157)") (class "Default")
      (node (ref "J1") (pin "157") (pinfunction "157_157") (pintype "passive+no_connect"))
    )
    (net (code "223") (name "unconnected-(J1-Pad158)") (class "Default")
      (node (ref "J1") (pin "158") (pinfunction "158_158") (pintype "passive+no_connect"))
    )
    (net (code "224") (name "unconnected-(J1-SCL-Pad34)") (class "Default")
      (node (ref "J1") (pin "34") (pinfunction "SCL_34") (pintype "passive"))
    )
    (net (code "225") (name "unconnected-(J1-SDA-Pad33)") (class "Default")
      (node (ref "J1") (pin "33") (pinfunction "SDA_33") (pintype "passive"))
    )
    (net (code "226") (name "unconnected-(J1-TCK-Pad35)") (class "Default")
      (node (ref "J1") (pin "35") (pinfunction "TCK_35") (pintype "passive"))
    )
    (net (code "227") (name "unconnected-(J1-TDI-Pad38)") (class "Default")
      (node (ref "J1") (pin "38") (pinfunction "TDI_38") (pintype "passive"))
    )
    (net (code "228") (name "unconnected-(J1-TDO-Pad37)") (class "Default")
      (node (ref "J1") (pin "37") (pinfunction "TDO_37") (pintype "passive"))
    )
    (net (code "229") (name "unconnected-(J1-TMS-Pad36)") (class "Default")
      (node (ref "J1") (pin "36") (pinfunction "TMS_36") (pintype "passive"))
    )
    (net (code "230") (name "unconnected-(U1-B3-Pad19)") (class "Default")
      (node (ref "U1") (pin "19") (pinfunction "B3_19") (pintype "passive+no_connect"))
    )
    (net (code "231") (name "unconnected-(U1-B4-Pad18)") (class "Default")
      (node (ref "U1") (pin "18") (pinfunction "B4_18") (pintype "passive+no_connect"))
    )
    (net (code "232") (name "unconnected-(U1-B5-Pad17)") (class "Default")
      (node (ref "U1") (pin "17") (pinfunction "B5_17") (pintype "passive+no_connect"))
    )
    (net (code "233") (name "unconnected-(U1-B6-Pad16)") (class "Default")
      (node (ref "U1") (pin "16") (pinfunction "B6_16") (pintype "passive+no_connect"))
    )
    (net (code "234") (name "unconnected-(U1-B7-Pad15)") (class "Default")
      (node (ref "U1") (pin "15") (pinfunction "B7_15") (pintype "passive+no_connect"))
    )
    (net (code "235") (name "unconnected-(U1-B8-Pad14)") (class "Default")
      (node (ref "U1") (pin "14") (pinfunction "B8_14") (pintype "passive+no_connect"))
    )
    (net (code "236") (name "unconnected-(U3-A7-Pad9)") (class "Default")
      (node (ref "U3") (pin "9") (pinfunction "A7_9") (pintype "passive+no_connect"))
    )
    (net (code "237") (name "unconnected-(U3-A8-Pad10)") (class "Default")
      (node (ref "U3") (pin "10") (pinfunction "A8_10") (pintype "passive+no_connect"))
    )
    (net (code "238") (name "unconnected-(U3-B7-Pad15)") (class "Default")
      (node (ref "U3") (pin "15") (pinfunction "B7_15") (pintype "passive+no_connect"))
    )
    (net (code "239") (name "unconnected-(U3-B8-Pad14)") (class "Default")
      (node (ref "U3") (pin "14") (pinfunction "B8_14") (pintype "passive+no_connect"))
    )
    (net (code "240") (name "unconnected-(U4-CLKOUT1-Pad5)") (class "Default")
      (node (ref "U4") (pin "5") (pinfunction "CLKOUT1_5") (pintype "output+no_connect"))
    )
    (net (code "241") (name "unconnected-(U4-CLKOUT2-Pad13)") (class "Default")
      (node (ref "U4") (pin "13") (pinfunction "CLKOUT2_13") (pintype "output+no_connect"))
    )
    (net (code "242") (name "unconnected-(U4-CLKOUT3-Pad15)") (class "Default")
      (node (ref "U4") (pin "15") (pinfunction "CLKOUT3_15") (pintype "output+no_connect"))
    )
    (net (code "243") (name "unconnected-(U4-CLKOUT4-Pad17)") (class "Default")
      (node (ref "U4") (pin "17") (pinfunction "CLKOUT4_17") (pintype "output+no_connect"))
    )
    (net (code "244") (name "unconnected-(U4-OSCOUT-Pad10)") (class "Default")
      (node (ref "U4") (pin "10") (pinfunction "OSCOUT_10") (pintype "output+no_connect"))
    )
    (net (code "245") (name "unconnected-(U5-CLKOUT2-Pad13)") (class "Default")
      (node (ref "U5") (pin "13") (pinfunction "CLKOUT2_13") (pintype "output+no_connect"))
    )
    (net (code "246") (name "unconnected-(U5-CLKOUT3-Pad15)") (class "Default")
      (node (ref "U5") (pin "15") (pinfunction "CLKOUT3_15") (pintype "output+no_connect"))
    )
    (net (code "247") (name "unconnected-(U5-CLKOUT4-Pad17)") (class "Default")
      (node (ref "U5") (pin "17") (pinfunction "CLKOUT4_17") (pintype "output+no_connect"))
    )
    (net (code "248") (name "unconnected-(U5-OSCOUT-Pad10)") (class "Default")
      (node (ref "U5") (pin "10") (pinfunction "OSCOUT_10") (pintype "output+no_connect"))
    )
  )
)
